# led-light.net
KiCad netlist of a schematic drawn in EAGLE
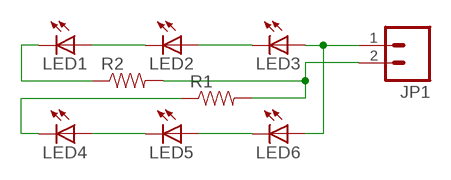
[diagram p0: schematic, sheet 1]

(export (version "E")
  (design (tool "Eeschema 10.0.6"))
  (components
    (comp (ref "JP1")
      (value "M02PTH")
      (footprint "eagle-import:1X02")
      (libsource (lib "eagle-import") (part "M02PTH"))
    )
    (comp (ref "LED1")
      (value "LED5MM")
      (footprint "eagle-import:LED5MM")
      (libsource (lib "eagle-import") (part "LED5MM"))
    )
    (comp (ref "LED2")
      (value "LED5MM")
      (footprint "eagle-import:LED5MM")
      (libsource (lib "eagle-import") (part "LED5MM"))
    )
    (comp (ref "LED3")
      (value "LED5MM")
      (footprint "eagle-import:LED5MM")
      (libsource (lib "eagle-import") (part "LED5MM"))
    )
    (comp (ref "LED4")
      (value "LED5MM")
      (footprint "eagle-import:LED5MM")
      (libsource (lib "eagle-import") (part "LED5MM"))
    )
    (comp (ref "LED5")
      (value "LED5MM")
      (footprint "eagle-import:LED5MM")
      (libsource (lib "eagle-import") (part "LED5MM"))
    )
    (comp (ref "LED6")
      (value "LED5MM")
      (footprint "eagle-import:LED5MM")
      (libsource (lib "eagle-import") (part "LED5MM"))
    )
    (comp (ref "R1")
      (value "RESISTORPTH-1/4W")
      (footprint "eagle-import:AXIAL-0.4")
      (libsource (lib "eagle-import") (part "RESISTORPTH-1/4W"))
    )
    (comp (ref "R2")
      (value "RESISTORPTH-1/4W")
      (footprint "eagle-import:AXIAL-0.4")
      (libsource (lib "eagle-import") (part "RESISTORPTH-1/4W"))
    )
  )
  (nets
    (net (code "1") (name "Net-(JP1-Pad1)") (class "Default")
      (node (ref "JP1") (pin "1") (pinfunction "1_1") (pintype "passive"))
      (node (ref "LED3") (pin "A") (pinfunction "A_A") (pintype "passive"))
      (node (ref "LED6") (pin "A") (pinfunction "A_A") (pintype "passive"))
    )
    (net (code "2") (name "Net-(LED1-C)") (class "Default")
      (node (ref "LED1") (pin "K") (pinfunction "C_K") (pintype "passive"))
      (node (ref "R2") (pin "P$1") (pinfunction "1_P$1") (pintype "passive"))
    )
    (net (code "3") (name "Net-(LED2-C)") (class "Default")
      (node (ref "LED1") (pin "A") (pinfunction "A_A") (pintype "passive"))
      (node (ref "LED2") (pin "K") (pinfunction "C_K") (pintype "passive"))
    )
    (net (code "4") (name "Net-(LED3-C)") (class "Default")
      (node (ref "LED2") (pin "A") (pinfunction "A_A") (pintype "passive"))
      (node (ref "LED3") (pin "K") (pinfunction "C_K") (pintype "passive"))
    )
    (net (code "5") (name "Net-(LED4-C)") (class "Default")
      (node (ref "LED4") (pin "K") (pinfunction "C_K") (pintype "passive"))
      (node (ref "R1") (pin "P$1") (pinfunction "1_P$1") (pintype "passive"))
    )
    (net (code "6") (name "Net-(LED5-C)") (class "Default")
      (node (ref "LED4") (pin "A") (pinfunction "A_A") (pintype "passive"))
      (node (ref "LED5") (pin "K") (pinfunction "C_K") (pintype "passive"))
    )
    (net (code "7") (name "Net-(LED6-C)") (class "Default")
      (node (ref "LED5") (pin "A") (pinfunction "A_A") (pintype "passive"))
      (node (ref "LED6") (pin "K") (pinfunction "C_K") (pintype "passive"))
    )
    (net (code "8") (name "Net-(R1-2)") (class "Default")
      (node (ref "JP1") (pin "2") (pinfunction "2_2") (pintype "passive"))
      (node (ref "R1") (pin "P$2") (pinfunction "2_P$2") (pintype "passive"))
      (node (ref "R2") (pin "P$2") (pinfunction "2_P$2") (pintype "passive"))
    )
  )
)
